# 2DD-17-mk-1_4.net
KiCad netlist of a schematic drawn in EAGLE
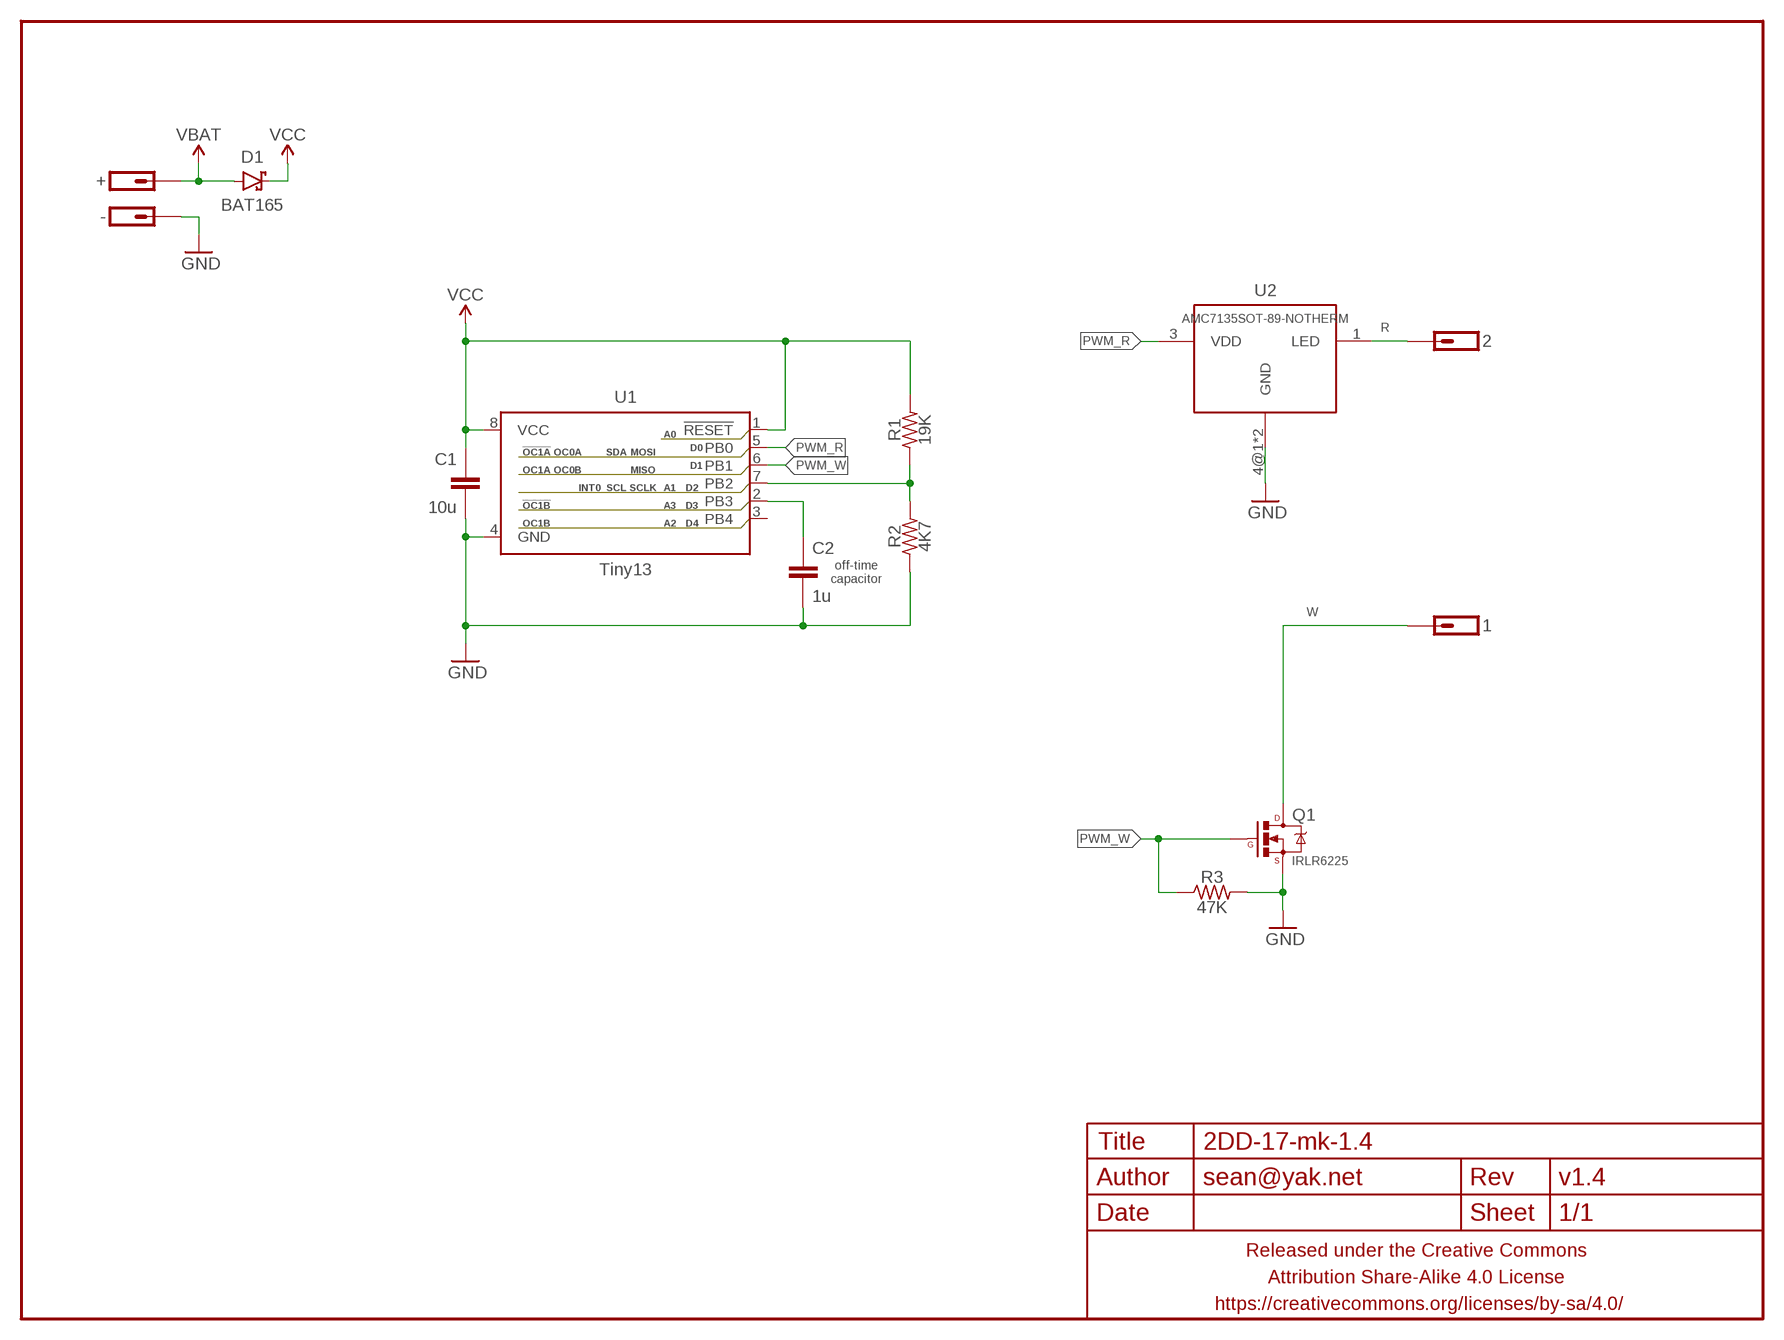
[diagram p0: schematic, sheet 1]

(export (version "E")
  (design (tool "Eeschema 10.0.6"))
  (components
    (comp (ref "+")
      (value "M01PTH-1MM-CIR-NS")
      (footprint "eagle-import:1X01-1MM-CIR-NS")
      (libsource (lib "eagle-import") (part "M01PTH-1MM-CIR-NS"))
    )
    (comp (ref "-")
      (value "M01NOT-A-VIA-NOPE")
      (footprint "eagle-import:1X01_NOSILK_NOSTOP")
      (libsource (lib "eagle-import") (part "M01NOT-A-VIA-NOPE"))
    )
    (comp (ref "1")
      (value "M01PTH-1MM-CIR-NS")
      (footprint "eagle-import:1X01-1MM-CIR-NS")
      (libsource (lib "eagle-import") (part "M01PTH-1MM-CIR-NS"))
    )
    (comp (ref "2")
      (value "M01SMD-1.25MM-DIA")
      (footprint "eagle-import:1X01-SMD-1.25MM-DIA-NS")
      (libsource (lib "eagle-import") (part "M01SMD-1.25MM-DIA"))
    )
    (comp (ref "C1")
      (value "10u")
      (footprint "eagle-import:C0603-TIGHTER")
      (libsource (lib "eagle-import") (part "CAPACITOR-CERAMICC0603-TIGHTER"))
    )
    (comp (ref "C2")
      (value "1u")
      (footprint "eagle-import:C0402")
      (libsource (lib "eagle-import") (part "CAPACITOR-CERAMICC0402"))
    )
    (comp (ref "D1")
      (value "BAT165")
      (footprint "eagle-import:SOD323-SCHOTTKY")
      (libsource (lib "eagle-import") (part "DIODE-SCHOTTKYSOD323"))
    )
    (comp (ref "FRAME1")
      (value "FRAME-LETTERNO_PACKAGE")
      (footprint "eagle-import:DUMMY")
      (fields (field (name "DESIGNER") "sean@yak.net") (field (name "VERSION") "v1.4"))
      (libsource (lib "eagle-import") (part "FRAME-LETTERNO_PACKAGE"))
    )
    (comp (ref "Q1")
      (value "IRLR6225")
      (footprint "eagle-import:SOT223-CLOSER")
      (libsource (lib "eagle-import") (part "MOSFET-NCHANNELSOT-223-CLOSER"))
    )
    (comp (ref "R1")
      (value "19K")
      (footprint "eagle-import:R0603-TIGHTER")
      (libsource (lib "eagle-import") (part "RESISTORR0603-TIGHTER"))
    )
    (comp (ref "R2")
      (value "4K7")
      (footprint "eagle-import:R0603-TIGHTER")
      (libsource (lib "eagle-import") (part "RESISTORR0603-TIGHTER"))
    )
    (comp (ref "R3")
      (value "47K")
      (footprint "eagle-import:R0603-TIGHTER")
      (libsource (lib "eagle-import") (part "RESISTORR0603-TIGHTER"))
    )
    (comp (ref "U1")
      (value "Tiny13")
      (footprint "eagle-import:SO08-NARROWER")
      (libsource (lib "eagle-import") (part "ATTINY13SOIC-NARROWPADS"))
    )
    (comp (ref "U2")
      (value "AMC7135SOT-89-NOTHERM")
      (footprint "eagle-import:SOT89-NOTHERM")
      (libsource (lib "eagle-import") (part "AMC7135SOT-89-NOTHERM"))
    )
  )
  (nets
    (net (code "1") (name "/R") (class "Default")
      (node (ref "2") (pin "P$1") (pinfunction "1_P$1") (pintype "passive"))
      (node (ref "U2") (pin "1") (pinfunction "LED_1") (pintype "bidirectional"))
    )
    (net (code "2") (name "/W") (class "Default")
      (node (ref "1") (pin "1") (pinfunction "1_1") (pintype "passive"))
      (node (ref "Q1") (pin "2") (pinfunction "D_2") (pintype "passive"))
      (node (ref "Q1") (pin "4") (pinfunction "D_4") (pintype "passive"))
    )
    (net (code "3") (name "GND") (class "Default")
      (node (ref "-") (pin "P$1") (pinfunction "1_P$1") (pintype "passive"))
      (node (ref "C1") (pin "2") (pinfunction "2_2") (pintype "passive"))
      (node (ref "C2") (pin "2") (pinfunction "2_2") (pintype "passive"))
      (node (ref "Q1") (pin "3") (pinfunction "S_3") (pintype "passive"))
      (node (ref "R2") (pin "1") (pinfunction "1_1") (pintype "passive"))
      (node (ref "R3") (pin "2") (pinfunction "2_2") (pintype "passive"))
      (node (ref "U1") (pin "4") (pinfunction "GND_4") (pintype "bidirectional"))
      (node (ref "U2") (pin "4@1") (pinfunction "GND_4@1") (pintype "bidirectional"))
      (node (ref "U2") (pin "4@2") (pinfunction "GND_4@2") (pintype "bidirectional"))
    )
    (net (code "4") (name "Net-(U1-PB2)") (class "Default")
      (node (ref "R1") (pin "1") (pinfunction "1_1") (pintype "passive"))
      (node (ref "R2") (pin "2") (pinfunction "2_2") (pintype "passive"))
      (node (ref "U1") (pin "7") (pinfunction "PB2_7") (pintype "bidirectional"))
    )
    (net (code "5") (name "Net-(U1-PB3)") (class "Default")
      (node (ref "C2") (pin "1") (pinfunction "1_1") (pintype "passive"))
      (node (ref "U1") (pin "2") (pinfunction "PB3_2") (pintype "bidirectional"))
    )
    (net (code "6") (name "PWM_R") (class "Default")
      (node (ref "U1") (pin "5") (pinfunction "PB0_5") (pintype "bidirectional"))
      (node (ref "U2") (pin "3") (pinfunction "VDD_3") (pintype "bidirectional"))
    )
    (net (code "7") (name "PWM_W") (class "Default")
      (node (ref "Q1") (pin "1") (pinfunction "G_1") (pintype "passive"))
      (node (ref "R3") (pin "1") (pinfunction "1_1") (pintype "passive"))
      (node (ref "U1") (pin "6") (pinfunction "PB1_6") (pintype "bidirectional"))
    )
    (net (code "8") (name "VBAT") (class "Default")
      (node (ref "+") (pin "1") (pinfunction "1_1") (pintype "passive"))
      (node (ref "D1") (pin "A") (pinfunction "A_A") (pintype "passive"))
    )
    (net (code "9") (name "VCC") (class "Default")
      (node (ref "C1") (pin "1") (pinfunction "1_1") (pintype "passive"))
      (node (ref "D1") (pin "C") (pinfunction "C_C") (pintype "passive"))
      (node (ref "R1") (pin "2") (pinfunction "2_2") (pintype "passive"))
      (node (ref "U1") (pin "1") (pinfunction "~{RESET}_1") (pintype "bidirectional"))
      (node (ref "U1") (pin "8") (pinfunction "VCC_8") (pintype "bidirectional"))
    )
    (net (code "10") (name "unconnected-(U1-PB4-Pad3)") (class "Default")
      (node (ref "U1") (pin "3") (pinfunction "PB4_3") (pintype "bidirectional"))
    )
  )
)
